# Simple-PWM-Fan-controller_v2.net
KiCad netlist of a schematic drawn in EAGLE
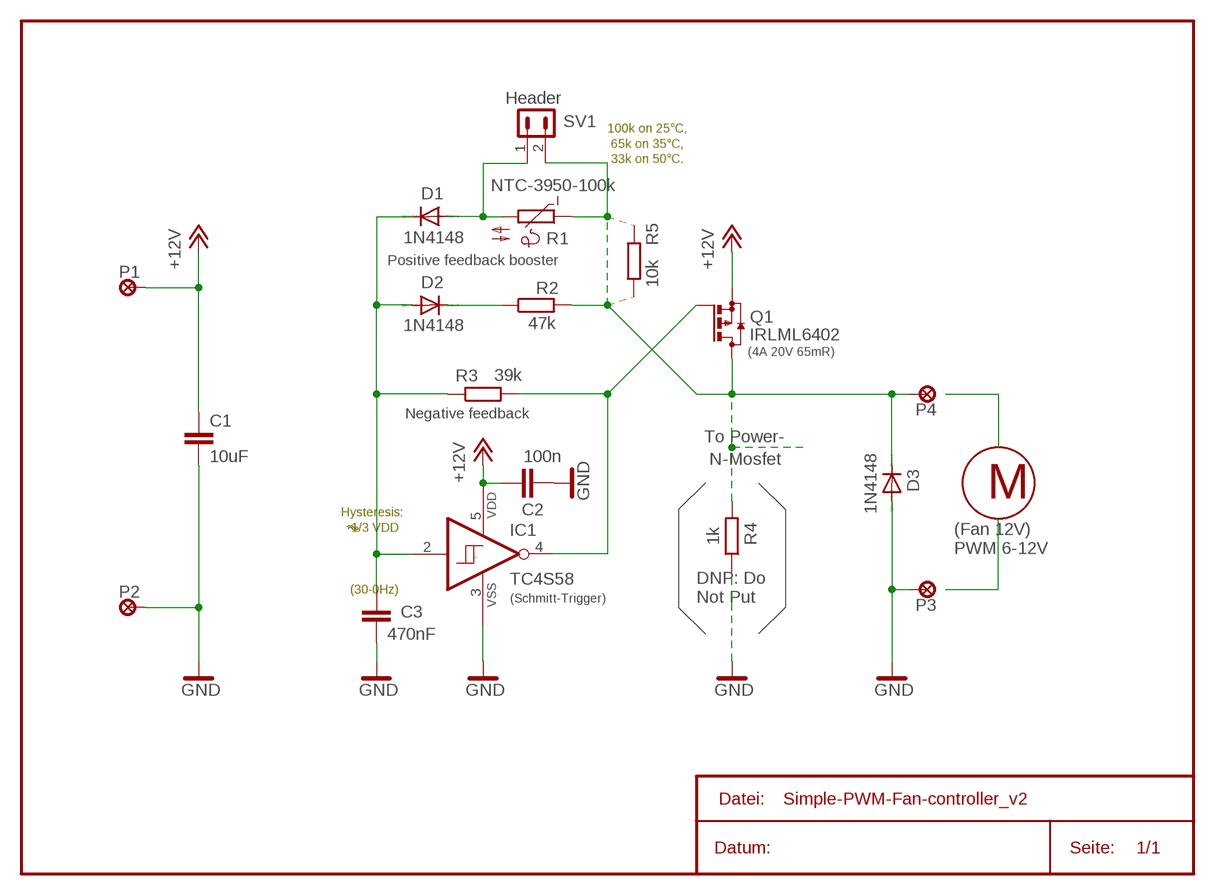
[diagram p0: schematic, sheet 1]

(export (version "E")
  (design (tool "Eeschema 10.0.6"))
  (components
    (comp (ref "C1")
      (value "10uF")
      (footprint "eagle-import:C1206")
      (libsource (lib "eagle-import") (part "C-EUC1206"))
    )
    (comp (ref "C2")
      (value "100n")
      (footprint "eagle-import:C0603")
      (libsource (lib "eagle-import") (part "C-EUC0603"))
    )
    (comp (ref "C3")
      (value "470nF")
      (footprint "eagle-import:C0603")
      (libsource (lib "eagle-import") (part "C-EUC0603"))
    )
    (comp (ref "D1")
      (value "1N4148")
      (footprint "eagle-import:SOD323-R")
      (libsource (lib "eagle-import") (part "DIODE-SOD323-R"))
    )
    (comp (ref "D2")
      (value "1N4148")
      (footprint "eagle-import:SOD323-R")
      (libsource (lib "eagle-import") (part "DIODE-SOD323-R"))
    )
    (comp (ref "D3")
      (value "1N4148")
      (footprint "eagle-import:SOD323-R")
      (libsource (lib "eagle-import") (part "DIODE-SOD323-R"))
    )
    (comp (ref "IC1")
      (value "TC4S58")
      (footprint "eagle-import:SSOP5P09")
      (libsource (lib "eagle-import") (part "TC4S584"))
    )
    (comp (ref "P1")
      (value "LSP17")
      (footprint "eagle-import:LSP17")
      (libsource (lib "eagle-import") (part "LSP17"))
    )
    (comp (ref "P2")
      (value "LSP17")
      (footprint "eagle-import:LSP17")
      (libsource (lib "eagle-import") (part "LSP17"))
    )
    (comp (ref "P3")
      (value "LSP17")
      (footprint "eagle-import:LSP17")
      (libsource (lib "eagle-import") (part "LSP17"))
    )
    (comp (ref "P4")
      (value "LSP17")
      (footprint "eagle-import:LSP17")
      (libsource (lib "eagle-import") (part "LSP17"))
    )
    (comp (ref "Q1")
      (value "IRLML6402")
      (footprint "eagle-import:SOT23")
      (libsource (lib "eagle-import") (part "BSS8423"))
    )
    (comp (ref "R1")
      (value "NTC-3950-100k")
      (footprint "eagle-import:P640")
      (libsource (lib "eagle-import") (part "NTC640"))
    )
    (comp (ref "R2")
      (value "47k")
      (footprint "eagle-import:R0603")
      (libsource (lib "eagle-import") (part "R-EU_R0603"))
    )
    (comp (ref "R3")
      (value "39k")
      (footprint "eagle-import:R0603")
      (libsource (lib "eagle-import") (part "R-EU_R0603"))
    )
    (comp (ref "R4")
      (value "1k")
      (footprint "eagle-import:R0805")
      (libsource (lib "eagle-import") (part "R-EU_R0805"))
    )
    (comp (ref "R5")
      (value "10k")
      (footprint "eagle-import:R0603")
      (libsource (lib "eagle-import") (part "R-EU_R0603"))
    )
    (comp (ref "SV1")
      (value "Header")
      (footprint "eagle-import:MA02-1R")
      (libsource (lib "eagle-import") (part "MA02-11"))
    )
  )
  (nets
    (net (code "1") (name "+12V") (class "Default")
      (node (ref "C1") (pin "1") (pinfunction "1_1") (pintype "passive"))
      (node (ref "C2") (pin "1") (pinfunction "1_1") (pintype "passive"))
      (node (ref "IC1") (pin "5") (pinfunction "VDD_5") (pintype "power_in"))
      (node (ref "P1") (pin "P$1") (pinfunction "MP_P$1") (pintype "passive"))
      (node (ref "Q1") (pin "2") (pinfunction "S_2") (pintype "passive"))
    )
    (net (code "2") (name "GND") (class "Default")
      (node (ref "C1") (pin "2") (pinfunction "2_2") (pintype "passive"))
      (node (ref "C2") (pin "2") (pinfunction "2_2") (pintype "passive"))
      (node (ref "C3") (pin "2") (pinfunction "2_2") (pintype "passive"))
      (node (ref "D3") (pin "A") (pinfunction "A_A") (pintype "passive"))
      (node (ref "IC1") (pin "3") (pinfunction "VSS_3") (pintype "power_in"))
      (node (ref "P2") (pin "P$1") (pinfunction "MP_P$1") (pintype "passive"))
      (node (ref "P3") (pin "P$1") (pinfunction "MP_P$1") (pintype "passive"))
      (node (ref "R4") (pin "1") (pinfunction "1_1") (pintype "passive"))
    )
    (net (code "3") (name "Net-(D1-PadA)") (class "Default")
      (node (ref "D1") (pin "A") (pinfunction "A_A") (pintype "passive"))
      (node (ref "R1") (pin "2") (pinfunction "2_2") (pintype "passive"))
      (node (ref "SV1") (pin "1") (pinfunction "1_1") (pintype "passive"))
    )
    (net (code "4") (name "Net-(D2-PadC)") (class "Default")
      (node (ref "D2") (pin "C") (pinfunction "C_C") (pintype "passive"))
      (node (ref "R2") (pin "1") (pinfunction "1_1") (pintype "passive"))
    )
    (net (code "5") (name "Net-(IC1A-I)") (class "Default")
      (node (ref "C3") (pin "1") (pinfunction "1_1") (pintype "passive"))
      (node (ref "D1") (pin "C") (pinfunction "C_C") (pintype "passive"))
      (node (ref "D2") (pin "A") (pinfunction "A_A") (pintype "passive"))
      (node (ref "IC1") (pin "2") (pinfunction "I_2") (pintype "input"))
      (node (ref "R3") (pin "1") (pinfunction "1_1") (pintype "passive"))
    )
    (net (code "6") (name "Net-(IC1A-O)") (class "Default")
      (node (ref "IC1") (pin "4") (pinfunction "O_4") (pintype "output"))
      (node (ref "Q1") (pin "1") (pinfunction "G_1") (pintype "passive"))
      (node (ref "R3") (pin "2") (pinfunction "2_2") (pintype "passive"))
    )
    (net (code "7") (name "Net-(P4-MP)") (class "Default")
      (node (ref "D3") (pin "C") (pinfunction "C_C") (pintype "passive"))
      (node (ref "P4") (pin "P$1") (pinfunction "MP_P$1") (pintype "passive"))
      (node (ref "Q1") (pin "3") (pinfunction "D_3") (pintype "passive"))
      (node (ref "R1") (pin "1") (pinfunction "1_1") (pintype "passive"))
      (node (ref "R2") (pin "2") (pinfunction "2_2") (pintype "passive"))
      (node (ref "R4") (pin "2") (pinfunction "2_2") (pintype "passive"))
      (node (ref "SV1") (pin "2") (pinfunction "2_2") (pintype "passive"))
    )
    (net (code "8") (name "unconnected-(R5-Pad1)") (class "Default")
      (node (ref "R5") (pin "1") (pinfunction "1_1") (pintype "passive"))
    )
    (net (code "9") (name "unconnected-(R5-Pad2)") (class "Default")
      (node (ref "R5") (pin "2") (pinfunction "2_2") (pintype "passive"))
    )
  )
)
